# Pcb_teensy_swarm_robotics_schematic.net
KiCad netlist of a schematic drawn in Altium Designer
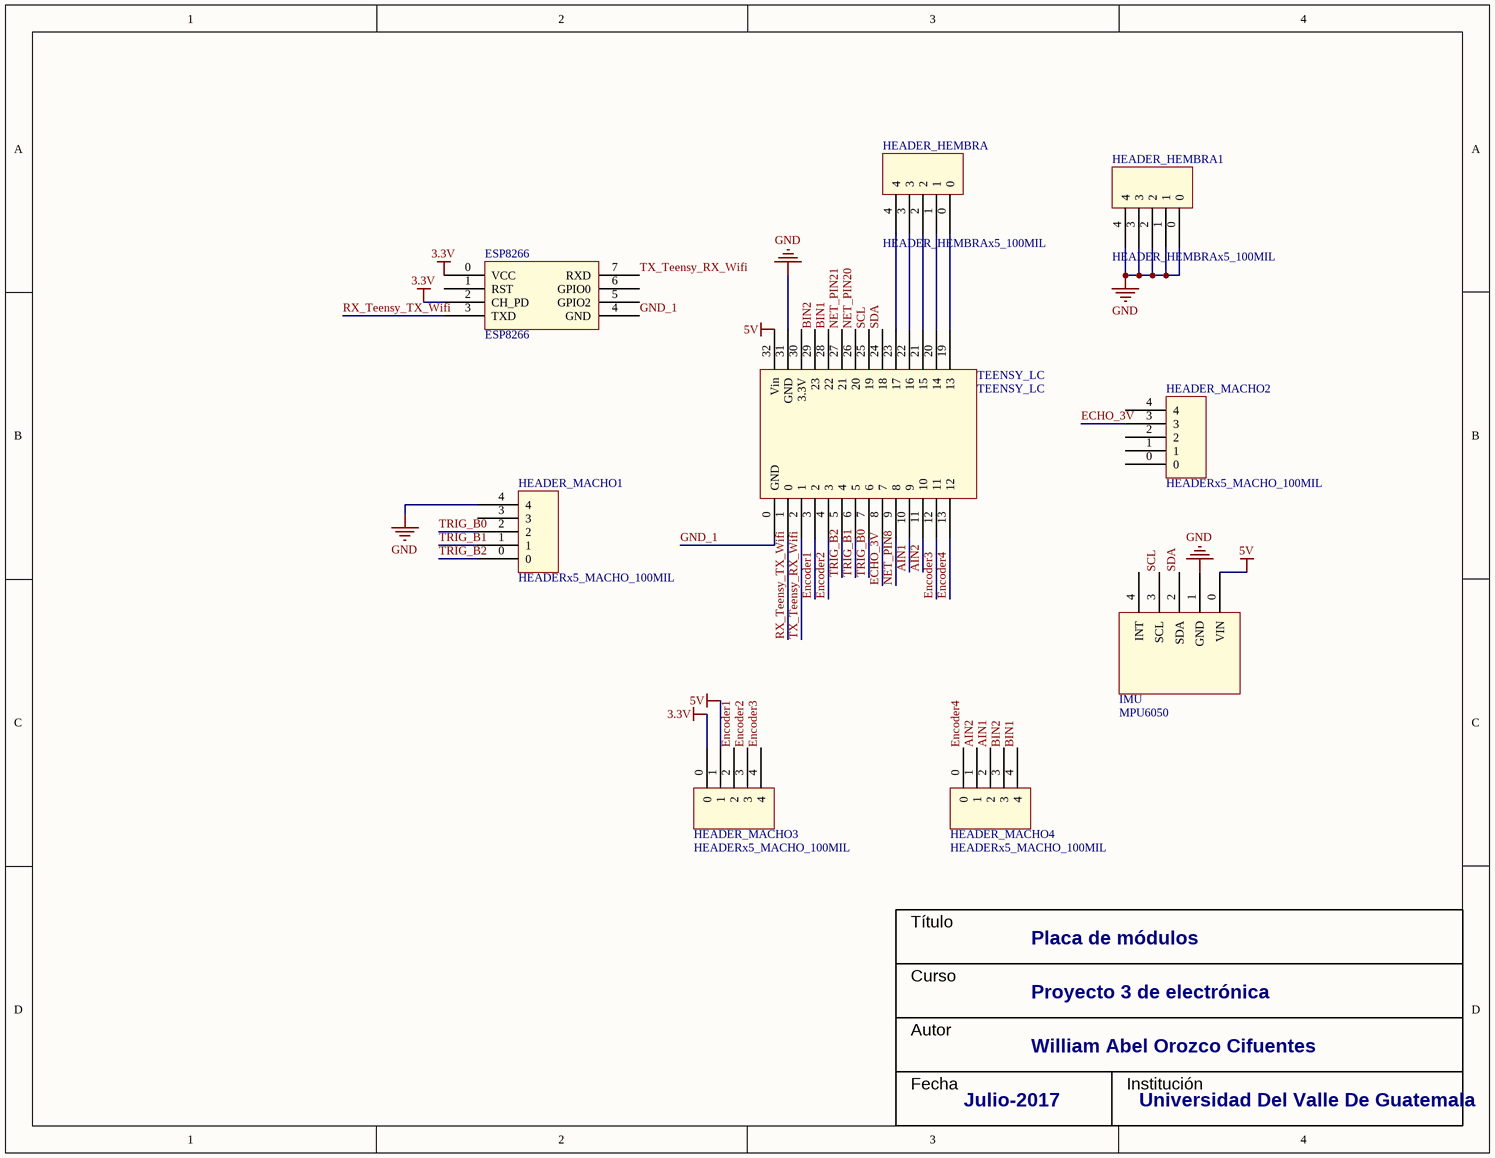
[diagram p0: Pcb_teensy_swarm_robotics_schematic.SchDoc]

(export (version "E")
  (design (tool "Eeschema 10.0.6"))
  (components
    (comp (ref "ESP8266")
      (value "ESP8266")
      (footprint "ESP8266")
      (libsource (lib "componentes_pcb_swarm_robotics") (part "ESP8266"))
    )
    (comp (ref "HEADER_HEMBRA")
      (value "HEADER_HEMBRAx5_100MIL")
      (footprint "HDRx5HEMBRA_FOOTPRINT")
      (libsource (lib "componentes_pcb_swarm_robotics") (part "HEADER_HEMBRAx5_100MIL"))
    )
    (comp (ref "HEADER_HEMBRA1")
      (value "HEADER_HEMBRAx5_100MIL")
      (footprint "HDRx5HEMBRA_FOOTPRINT")
      (libsource (lib "componentes_pcb_swarm_robotics") (part "HEADER_HEMBRAx5_100MIL"))
    )
    (comp (ref "HEADER_MACHO1")
      (value "HEADERx5_MACHO_100MIL")
      (footprint "HEADERx5_MACHO_FOOTPRINT")
      (libsource (lib "componentes_pcb_swarm_robotics") (part "HEADERx5_MACHO_100MIL"))
    )
    (comp (ref "HEADER_MACHO2")
      (value "HEADERx5_MACHO_100MIL")
      (footprint "HEADERx5_MACHO_FOOTPRINT")
      (libsource (lib "componentes_pcb_swarm_robotics") (part "HEADERx5_MACHO_100MIL"))
    )
    (comp (ref "HEADER_MACHO3")
      (value "HEADERx5_MACHO_100MIL")
      (footprint "HEADERx5_MACHO_FOOTPRINT")
      (libsource (lib "") (part "HEADERx5_MACHO_100MIL_1"))
    )
    (comp (ref "HEADER_MACHO4")
      (value "HEADERx5_MACHO_100MIL")
      (footprint "HEADERx5_MACHO_FOOTPRINT")
      (libsource (lib "") (part "HEADERx5_MACHO_100MIL_1"))
    )
    (comp (ref "IMU")
      (value "MPU6050")
      (footprint "IMU_")
      (libsource (lib "componentes_pcb_swarm_robotics") (part "MPU6050"))
    )
    (comp (ref "TEENSY_LC")
      (value "TEENSY_LC")
      (footprint "TEENSY_LC")
      (libsource (lib "componentes_pcb_swarm_robotics") (part "TEENSY_LC"))
    )
  )
  (nets
    (net (code "1") (name "/AIN1") (class "Default")
      (node (ref "HEADER_MACHO4") (pin "2") (pinfunction "2_2") (pintype "passive"))
      (node (ref "TEENSY_LC") (pin "10") (pinfunction "9_10") (pintype "passive"))
    )
    (net (code "2") (name "/AIN2") (class "Default")
      (node (ref "HEADER_MACHO4") (pin "1") (pinfunction "1_1") (pintype "passive"))
      (node (ref "TEENSY_LC") (pin "11") (pinfunction "10_11") (pintype "passive"))
    )
    (net (code "3") (name "/BIN1") (class "Default")
      (node (ref "HEADER_MACHO4") (pin "4") (pinfunction "4_4") (pintype "passive"))
      (node (ref "TEENSY_LC") (pin "28") (pinfunction "22_28") (pintype "passive"))
    )
    (net (code "4") (name "/BIN2") (class "Default")
      (node (ref "HEADER_MACHO4") (pin "3") (pinfunction "3_3") (pintype "passive"))
      (node (ref "TEENSY_LC") (pin "29") (pinfunction "23_29") (pintype "passive"))
    )
    (net (code "5") (name "/ECHO_3V") (class "Default")
      (node (ref "HEADER_MACHO2") (pin "3") (pinfunction "3_3") (pintype "passive"))
      (node (ref "TEENSY_LC") (pin "8") (pinfunction "7_8") (pintype "passive"))
    )
    (net (code "6") (name "/Encoder1") (class "Default")
      (node (ref "HEADER_MACHO3") (pin "2") (pinfunction "2_2") (pintype "passive"))
      (node (ref "TEENSY_LC") (pin "3") (pinfunction "2_3") (pintype "passive"))
    )
    (net (code "7") (name "/Encoder2") (class "Default")
      (node (ref "HEADER_MACHO3") (pin "3") (pinfunction "3_3") (pintype "passive"))
      (node (ref "TEENSY_LC") (pin "4") (pinfunction "3_4") (pintype "passive"))
    )
    (net (code "8") (name "/Encoder3") (class "Default")
      (node (ref "HEADER_MACHO3") (pin "4") (pinfunction "4_4") (pintype "passive"))
      (node (ref "TEENSY_LC") (pin "12") (pinfunction "11_12") (pintype "passive"))
    )
    (net (code "9") (name "/Encoder4") (class "Default")
      (node (ref "HEADER_MACHO4") (pin "0") (pinfunction "0_0") (pintype "passive"))
      (node (ref "TEENSY_LC") (pin "13") (pinfunction "12_13") (pintype "passive"))
    )
    (net (code "10") (name "/GND_1") (class "Default")
      (node (ref "ESP8266") (pin "4") (pinfunction "GND_4") (pintype "passive"))
      (node (ref "TEENSY_LC") (pin "0") (pinfunction "GND_0") (pintype "passive"))
    )
    (net (code "11") (name "/NET_PIN8") (class "Default")
      (node (ref "TEENSY_LC") (pin "9") (pinfunction "8_9") (pintype "passive"))
    )
    (net (code "12") (name "/NET_PIN20") (class "Default")
      (node (ref "TEENSY_LC") (pin "26") (pinfunction "20_26") (pintype "passive"))
    )
    (net (code "13") (name "/NET_PIN21") (class "Default")
      (node (ref "TEENSY_LC") (pin "27") (pinfunction "21_27") (pintype "passive"))
    )
    (net (code "14") (name "/RX_Teensy_TX_Wifi") (class "Default")
      (node (ref "ESP8266") (pin "3") (pinfunction "TXD_3") (pintype "passive"))
      (node (ref "TEENSY_LC") (pin "1") (pinfunction "0_1") (pintype "passive"))
    )
    (net (code "15") (name "/SCL") (class "Default")
      (node (ref "IMU") (pin "3") (pinfunction "SCL_3") (pintype "passive"))
      (node (ref "TEENSY_LC") (pin "25") (pinfunction "19_25") (pintype "passive"))
    )
    (net (code "16") (name "/SDA") (class "Default")
      (node (ref "IMU") (pin "2") (pinfunction "SDA_2") (pintype "passive"))
      (node (ref "TEENSY_LC") (pin "24") (pinfunction "18_24") (pintype "passive"))
    )
    (net (code "17") (name "/TRIG_B0") (class "Default")
      (node (ref "HEADER_MACHO1") (pin "2") (pinfunction "2_2") (pintype "passive"))
      (node (ref "TEENSY_LC") (pin "7") (pinfunction "6_7") (pintype "passive"))
    )
    (net (code "18") (name "/TRIG_B1") (class "Default")
      (node (ref "HEADER_MACHO1") (pin "1") (pinfunction "1_1") (pintype "passive"))
      (node (ref "TEENSY_LC") (pin "6") (pinfunction "5_6") (pintype "passive"))
    )
    (net (code "19") (name "/TRIG_B2") (class "Default")
      (node (ref "HEADER_MACHO1") (pin "0") (pinfunction "0_0") (pintype "passive"))
      (node (ref "TEENSY_LC") (pin "5") (pinfunction "4_5") (pintype "passive"))
    )
    (net (code "20") (name "/TX_Teensy_RX_Wifi") (class "Default")
      (node (ref "ESP8266") (pin "7") (pinfunction "RXD_7") (pintype "passive"))
      (node (ref "TEENSY_LC") (pin "2") (pinfunction "1_2") (pintype "passive"))
    )
    (net (code "21") (name "3.3V") (class "Default")
      (node (ref "ESP8266") (pin "0") (pinfunction "VCC_0") (pintype "passive"))
      (node (ref "ESP8266") (pin "2") (pinfunction "CH_PD_2") (pintype "passive"))
      (node (ref "HEADER_MACHO3") (pin "0") (pinfunction "0_0") (pintype "passive"))
    )
    (net (code "22") (name "5V") (class "Default")
      (node (ref "HEADER_MACHO3") (pin "1") (pinfunction "1_1") (pintype "passive"))
      (node (ref "IMU") (pin "0") (pinfunction "VIN_0") (pintype "passive"))
      (node (ref "TEENSY_LC") (pin "32") (pinfunction "Vin_32") (pintype "passive"))
    )
    (net (code "23") (name "GND") (class "Default")
      (node (ref "HEADER_HEMBRA1") (pin "0") (pinfunction "0_0") (pintype "passive"))
      (node (ref "HEADER_HEMBRA1") (pin "1") (pinfunction "1_1") (pintype "passive"))
      (node (ref "HEADER_HEMBRA1") (pin "2") (pinfunction "2_2") (pintype "passive"))
      (node (ref "HEADER_HEMBRA1") (pin "3") (pinfunction "3_3") (pintype "passive"))
      (node (ref "HEADER_HEMBRA1") (pin "4") (pinfunction "4_4") (pintype "passive"))
      (node (ref "HEADER_MACHO1") (pin "4") (pinfunction "4_4") (pintype "passive"))
      (node (ref "IMU") (pin "1") (pinfunction "GND_1") (pintype "passive"))
      (node (ref "TEENSY_LC") (pin "31") (pinfunction "GND_31") (pintype "passive"))
    )
    (net (code "24") (name "Net-(TEENSY_LC-13)") (class "Default")
      (node (ref "HEADER_HEMBRA") (pin "0") (pinfunction "0_0") (pintype "passive"))
      (node (ref "TEENSY_LC") (pin "19") (pinfunction "13_19") (pintype "passive"))
    )
    (net (code "25") (name "Net-(TEENSY_LC-14)") (class "Default")
      (node (ref "HEADER_HEMBRA") (pin "1") (pinfunction "1_1") (pintype "passive"))
      (node (ref "TEENSY_LC") (pin "20") (pinfunction "14_20") (pintype "passive"))
    )
    (net (code "26") (name "Net-(TEENSY_LC-15)") (class "Default")
      (node (ref "HEADER_HEMBRA") (pin "2") (pinfunction "2_2") (pintype "passive"))
      (node (ref "TEENSY_LC") (pin "21") (pinfunction "15_21") (pintype "passive"))
    )
    (net (code "27") (name "Net-(TEENSY_LC-16)") (class "Default")
      (node (ref "HEADER_HEMBRA") (pin "3") (pinfunction "3_3") (pintype "passive"))
      (node (ref "TEENSY_LC") (pin "22") (pinfunction "16_22") (pintype "passive"))
    )
    (net (code "28") (name "Net-(TEENSY_LC-17)") (class "Default")
      (node (ref "HEADER_HEMBRA") (pin "4") (pinfunction "4_4") (pintype "passive"))
      (node (ref "TEENSY_LC") (pin "23") (pinfunction "17_23") (pintype "passive"))
    )
    (net (code "29") (name "unconnected-(ESP8266-GPIO0-Pad6)") (class "Default")
      (node (ref "ESP8266") (pin "6") (pinfunction "GPIO0_6") (pintype "passive"))
    )
    (net (code "30") (name "unconnected-(ESP8266-GPIO2-Pad5)") (class "Default")
      (node (ref "ESP8266") (pin "5") (pinfunction "GPIO2_5") (pintype "passive"))
    )
    (net (code "31") (name "unconnected-(ESP8266-RST-Pad1)") (class "Default")
      (node (ref "ESP8266") (pin "1") (pinfunction "RST_1") (pintype "passive"))
    )
    (net (code "32") (name "unconnected-(HEADER_MACHO1-Pad3)") (class "Default")
      (node (ref "HEADER_MACHO1") (pin "3") (pinfunction "3_3") (pintype "passive"))
    )
    (net (code "33") (name "unconnected-(HEADER_MACHO2-Pad0)") (class "Default")
      (node (ref "HEADER_MACHO2") (pin "0") (pinfunction "0_0") (pintype "passive"))
    )
    (net (code "34") (name "unconnected-(HEADER_MACHO2-Pad1)") (class "Default")
      (node (ref "HEADER_MACHO2") (pin "1") (pinfunction "1_1") (pintype "passive"))
    )
    (net (code "35") (name "unconnected-(HEADER_MACHO2-Pad2)") (class "Default")
      (node (ref "HEADER_MACHO2") (pin "2") (pinfunction "2_2") (pintype "passive"))
    )
    (net (code "36") (name "unconnected-(HEADER_MACHO2-Pad4)") (class "Default")
      (node (ref "HEADER_MACHO2") (pin "4") (pinfunction "4_4") (pintype "passive"))
    )
    (net (code "37") (name "unconnected-(IMU-INT-Pad4)") (class "Default")
      (node (ref "IMU") (pin "4") (pinfunction "INT_4") (pintype "passive"))
    )
    (net (code "38") (name "unconnected-(TEENSY_LC-3.3V-Pad30)") (class "Default")
      (node (ref "TEENSY_LC") (pin "30") (pinfunction "3.3V_30") (pintype "passive"))
    )
  )
)
